# DS157-1_1-C.net
KiCad netlist of a schematic drawn in Altium Designer
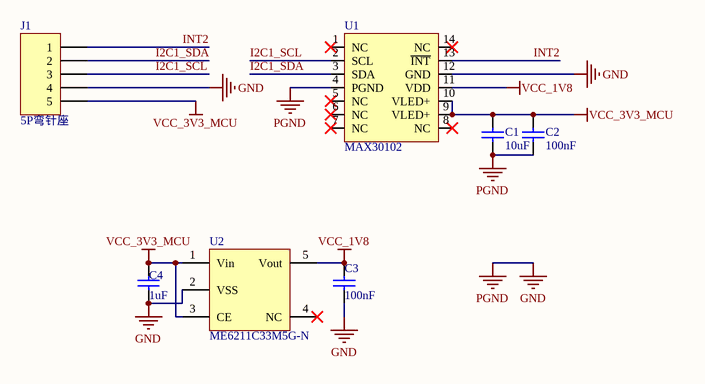
[diagram p0: DS157-1.1-C心率传感器.SchDoc]

(export (version "E")
  (design (tool "Eeschema 10.0.6"))
  (components
    (comp (ref "C1")
      (value "10uF")
      (footprint "0603CAP")
      (description "贴片电容")
      (fields (field (name "Comment") "SMDCAP00016"))
      (libsource (lib "AD_SCH") (part "MLCC 10uF 50V ±10％ 0603"))
    )
    (comp (ref "C2")
      (value "100nF")
      (footprint "0603CAP")
      (description "贴片电容")
      (fields (field (name "Comment") "SMDCAP00013"))
      (libsource (lib "AD_SCH") (part "MLCC 100nF 50V ±10％ 0603"))
    )
    (comp (ref "C3")
      (value "100nF")
      (footprint "0603CAP")
      (description "贴片电容")
      (fields (field (name "Comment") "SMDCAP00013"))
      (libsource (lib "AD_SCH") (part "MLCC 100nF 50V ±10％ 0603"))
    )
    (comp (ref "C4")
      (value "1uF")
      (footprint "0603CAP")
      (description "贴片电容")
      (fields (field (name "Comment") "SMDCAP00015"))
      (libsource (lib "AD_SCH") (part "MLCC 1uF 50V ±10％ 0603"))
    )
    (comp (ref "J1")
      (value "5P弯针座")
      (footprint "XH2.54-5PW")
      (fields (field (name "Comment") "SL000000035"))
      (libsource (lib "AD_SCH") (part "XH2.54mm-5AW 弯针座"))
    )
    (comp (ref "U1") (value "MAX30102") (footprint "OESIP-14") (libsource (lib "AD_SCH") (part "MAX30102")))
    (comp (ref "U2")
      (value "ME6211C33M5G-N")
      (footprint "SOT23-5")
      (description "稳压芯片")
      (libsource (lib "AD_SCH") (part "ME6211C33M5G-N"))
    )
  )
  (nets
    (net (code "1") (name "/I2C1_SCL") (class "Default")
      (node (ref "J1") (pin "3") (pinfunction "3_3") (pintype "passive"))
      (node (ref "U1") (pin "2") (pinfunction "SCL_2") (pintype "passive"))
    )
    (net (code "2") (name "/I2C1_SDA") (class "Default")
      (node (ref "J1") (pin "2") (pinfunction "2_2") (pintype "passive"))
      (node (ref "U1") (pin "3") (pinfunction "SDA_3") (pintype "passive"))
    )
    (net (code "3") (name "/INT2") (class "Default")
      (node (ref "J1") (pin "1") (pinfunction "1_1") (pintype "passive"))
      (node (ref "U1") (pin "13") (pinfunction "INT_13") (pintype "passive"))
    )
    (net (code "4") (name "GND") (class "Default")
      (node (ref "C1") (pin "1") (pinfunction "1_1") (pintype "passive"))
      (node (ref "C2") (pin "2") (pinfunction "2_2") (pintype "passive"))
      (node (ref "C3") (pin "1") (pinfunction "1_1") (pintype "passive"))
      (node (ref "C4") (pin "1") (pinfunction "1_1") (pintype "passive"))
      (node (ref "J1") (pin "4") (pinfunction "4_4") (pintype "passive"))
      (node (ref "U1") (pin "12") (pinfunction "GND_12") (pintype "passive"))
      (node (ref "U1") (pin "4") (pinfunction "PGND_4") (pintype "passive"))
      (node (ref "U2") (pin "2") (pinfunction "VSS_2") (pintype "passive"))
    )
    (net (code "5") (name "VCC_1V8") (class "Default")
      (node (ref "C3") (pin "2") (pinfunction "2_2") (pintype "passive"))
      (node (ref "U1") (pin "11") (pinfunction "VDD_11") (pintype "passive"))
      (node (ref "U2") (pin "5") (pinfunction "Vout_5") (pintype "passive"))
    )
    (net (code "6") (name "VCC_3V3_MCU") (class "Default")
      (node (ref "C1") (pin "2") (pinfunction "2_2") (pintype "passive"))
      (node (ref "C2") (pin "1") (pinfunction "1_1") (pintype "passive"))
      (node (ref "C4") (pin "2") (pinfunction "2_2") (pintype "passive"))
      (node (ref "J1") (pin "5") (pinfunction "5_5") (pintype "passive"))
      (node (ref "U1") (pin "10") (pinfunction "VLED+_10") (pintype "passive"))
      (node (ref "U1") (pin "9") (pinfunction "VLED+_9") (pintype "passive"))
      (node (ref "U2") (pin "1") (pinfunction "Vin_1") (pintype "passive"))
      (node (ref "U2") (pin "3") (pinfunction "CE_3") (pintype "passive"))
    )
    (net (code "7") (name "unconnected-(U1-NC-Pad1)") (class "Default")
      (node (ref "U1") (pin "1") (pinfunction "NC_1") (pintype "passive+no_connect"))
    )
    (net (code "8") (name "unconnected-(U1-NC-Pad5)") (class "Default")
      (node (ref "U1") (pin "5") (pinfunction "NC_5") (pintype "passive+no_connect"))
    )
    (net (code "9") (name "unconnected-(U1-NC-Pad6)") (class "Default")
      (node (ref "U1") (pin "6") (pinfunction "NC_6") (pintype "passive+no_connect"))
    )
    (net (code "10") (name "unconnected-(U1-NC-Pad7)") (class "Default")
      (node (ref "U1") (pin "7") (pinfunction "NC_7") (pintype "passive+no_connect"))
    )
    (net (code "11") (name "unconnected-(U1-NC-Pad8)") (class "Default")
      (node (ref "U1") (pin "8") (pinfunction "NC_8") (pintype "passive+no_connect"))
    )
    (net (code "12") (name "unconnected-(U1-NC-Pad14)") (class "Default")
      (node (ref "U1") (pin "14") (pinfunction "NC_14") (pintype "passive+no_connect"))
    )
    (net (code "13") (name "unconnected-(U2-NC-Pad4)") (class "Default")
      (node (ref "U2") (pin "4") (pinfunction "NC_4") (pintype "passive+no_connect"))
    )
  )
)
